# SCH_clock1_2025-09-26.net
KiCad netlist of a schematic drawn in EasyEDA
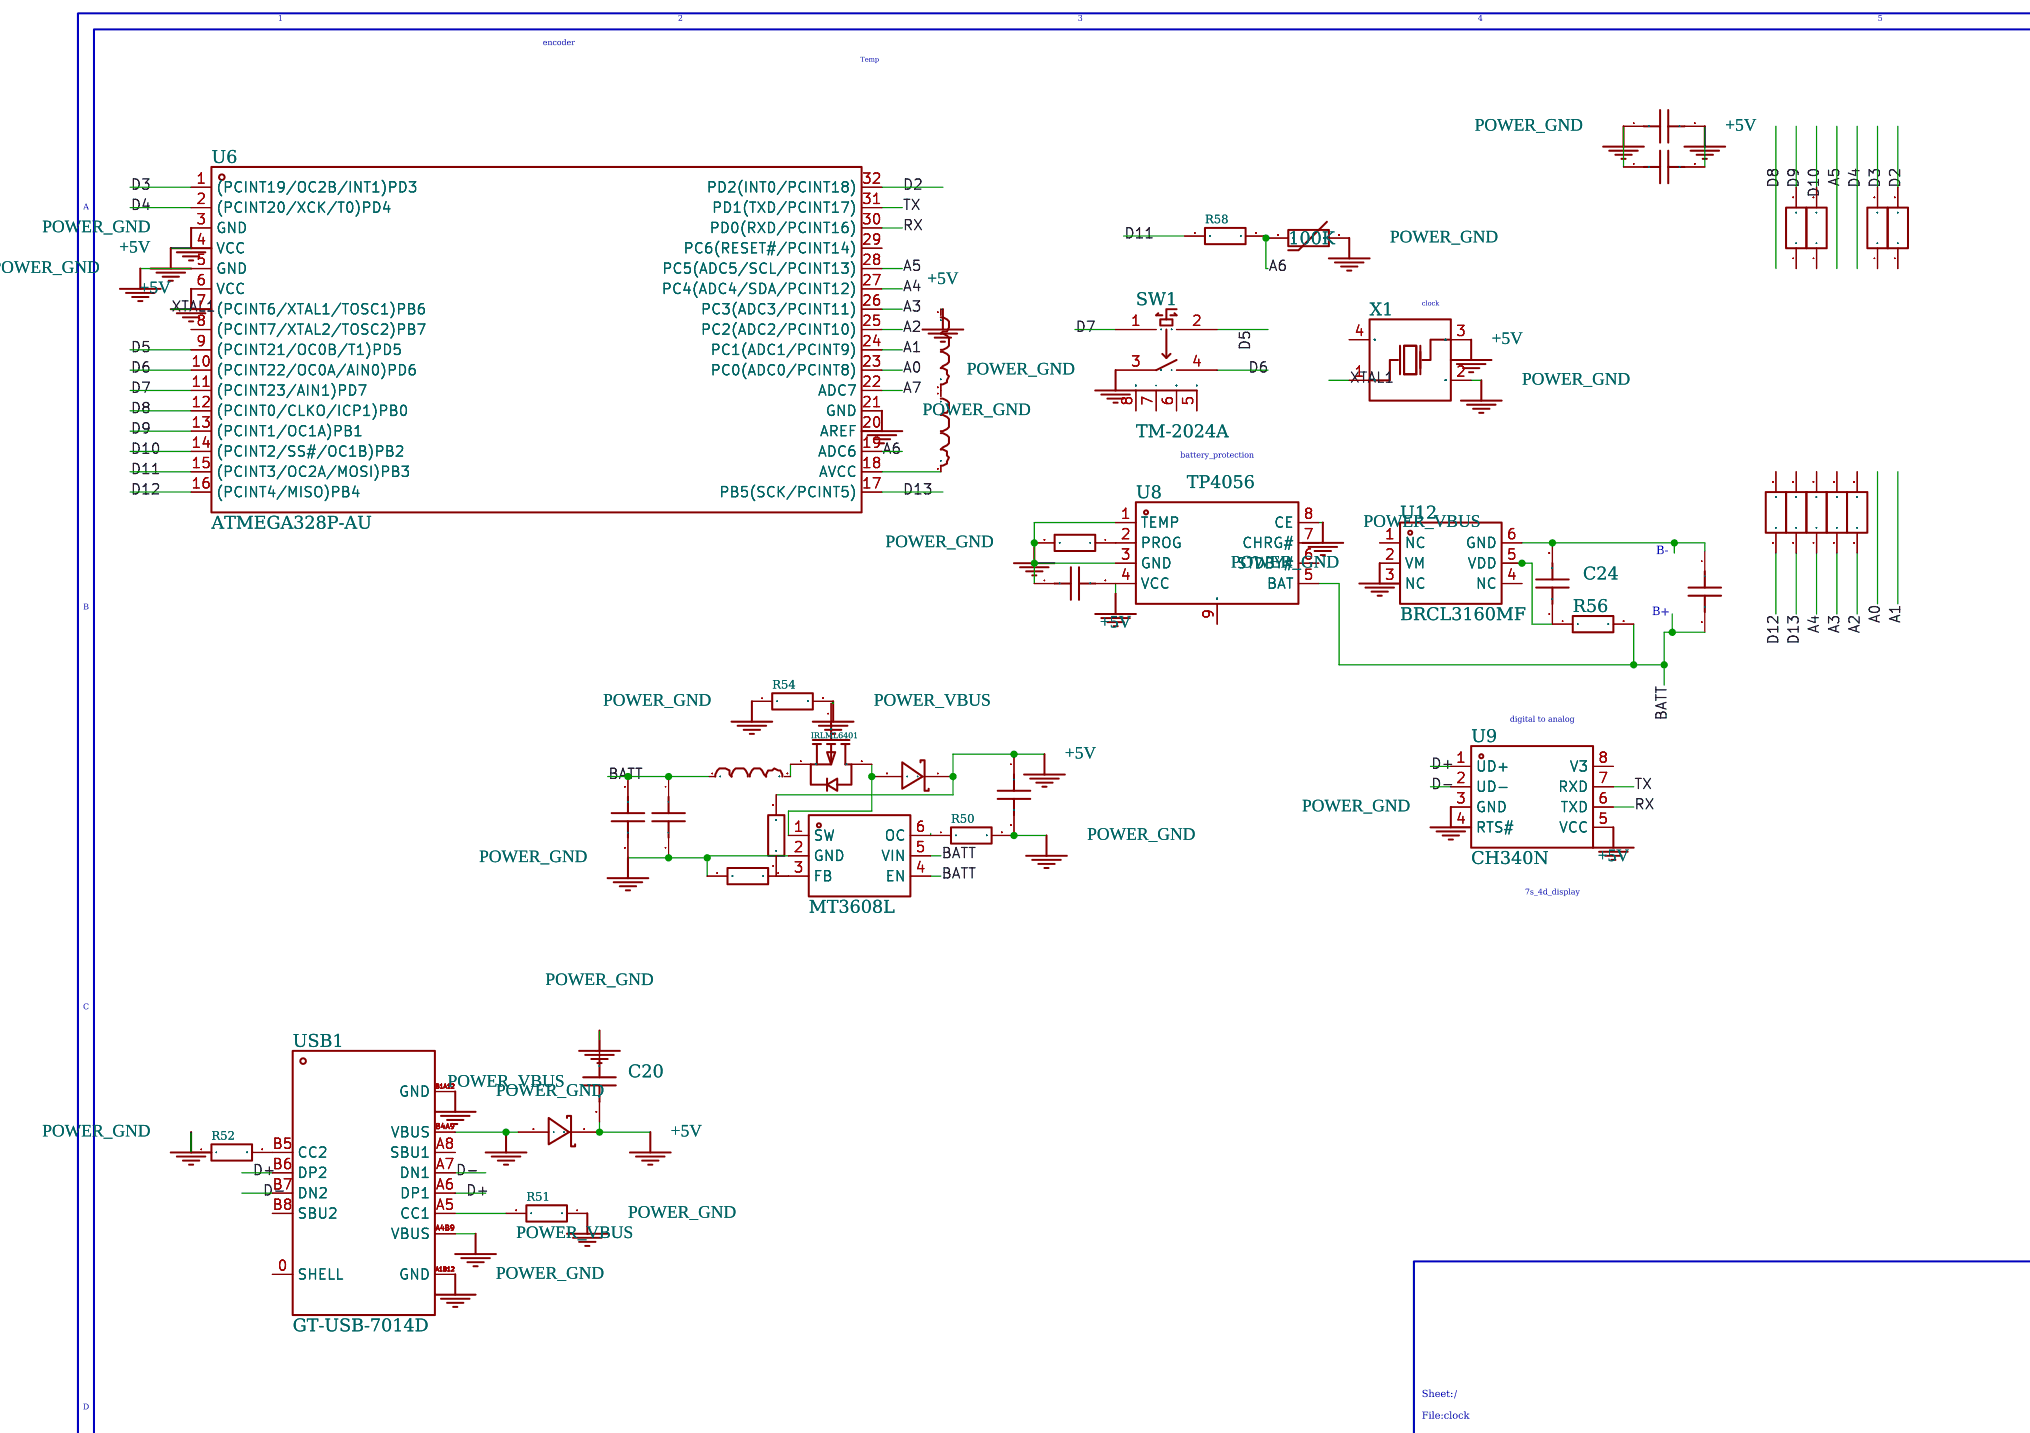
[diagram p0: schematic sheet]

(export (version "E")
  (design (tool "Eeschema 10.0.6"))
  (components
    (comp (ref "100K")
      (value "NCP03WF104F05RL")
      (fields (field (name "Manufacturer") "muRata(村田)"))
      (libsource (lib "") (part "Unknown_635_-660"))
    )
    (comp (ref "C15")
      (value "4.7uF")
      (fields
        (field (name "Manufacturer Part") "CL05A475MQ5NRNC")
        (field (name "Manufacturer") "SAMSUNG(三星)")
      )
      (libsource (lib "") (part "Unknown_300_-375"))
    )
    (comp (ref "C16")
      (value "4.7uF")
      (fields
        (field (name "Manufacturer Part") "CL05A475MQ5NRNC")
        (field (name "Manufacturer") "SAMSUNG(三星)")
      )
      (libsource (lib "") (part "Unknown_320_-375"))
    )
    (comp (ref "C19")
      (value "4.7uF")
      (fields
        (field (name "Manufacturer Part") "CL05A475MQ5NRNC")
        (field (name "Manufacturer") "SAMSUNG(三星)")
      )
      (libsource (lib "") (part "Unknown_520_-490"))
    )
    (comp (ref "C20")
      (value "4.7uF")
      (fields
        (field (name "Manufacturer Part") "CL05A475MQ5NRNC")
        (field (name "Manufacturer") "SAMSUNG(三星)")
      )
      (libsource (lib "") (part "Unknown_286_-245"))
    )
    (comp (ref "C21")
      (value "4.7uF")
      (fields
        (field (name "Manufacturer Part") "CL05A475MQ5NRNC")
        (field (name "Manufacturer") "SAMSUNG(三星)")
      )
      (libsource (lib "") (part "Unknown_490_-386"))
    )
    (comp (ref "C24")
      (value "100nF")
      (fields
        (field (name "Manufacturer Part") "FCC0402B104K160AT")
        (field (name "Manufacturer") "FOJAN(富捷)")
      )
      (libsource (lib "") (part "Unknown_755_-490"))
    )
    (comp (ref "C25")
      (value "4.7uF")
      (fields
        (field (name "Manufacturer Part") "CL05A475MQ5NRNC")
        (field (name "Manufacturer") "SAMSUNG(三星)")
      )
      (libsource (lib "") (part "Unknown_810_-715"))
    )
    (comp (ref "C27")
      (value "4.7uF")
      (fields
        (field (name "Manufacturer Part") "CL05A475MQ5NRNC")
        (field (name "Manufacturer") "SAMSUNG(三星)")
      )
      (libsource (lib "") (part "Unknown_810_-695"))
    )
    (comp (ref "C28")
      (value "4.7uF")
      (fields
        (field (name "Manufacturer Part") "CL05A475MQ5NRNC")
        (field (name "Manufacturer") "SAMSUNG(三星)")
      )
      (libsource (lib "") (part "Unknown_830_-486"))
    )
    (comp (ref "D5")
      (value "DSK34")
      (fields (field (name "Manufacturer") "MDD(辰达半导体)"))
      (libsource (lib "") (part "Unknown_440_-395"))
    )
    (comp (ref "D6")
      (value "DSK34")
      (fields (field (name "Manufacturer") "MDD(辰达半导体)"))
      (libsource (lib "") (part "Unknown_266_-220"))
    )
    (comp (ref "L3")
      (value "4.7uH")
      (fields (field (name "Manufacturer Part") "CMI321609U4R7KT") (field (name "Manufacturer") "FH(风华)"))
      (libsource (lib "") (part "Unknown_360_-395"))
    )
    (comp (ref "L5")
      (value "4.7uH")
      (fields (field (name "Manufacturer Part") "CMI321609U4R7KT") (field (name "Manufacturer") "FH(风华)"))
      (libsource (lib "") (part "Unknown_454_-565"))
    )
    (comp (ref "L6")
      (value "4.7uH")
      (fields (field (name "Manufacturer Part") "CMI321609U4R7KT") (field (name "Manufacturer") "FH(风华)"))
      (libsource (lib "") (part "Unknown_454_-605"))
    )
    (comp (ref "Q1")
      (value "IRLML6401")
      (fields (field (name "Manufacturer") "Hottech(合科泰)"))
      (libsource (lib "") (part "Unknown_400_-401"))
    )
    (comp (ref "R39")
      (value "1kΩ")
      (fields (field (name "Manufacturer Part") "FRC0603F1001TS") (field (name "Manufacturer") "FOJAN(富捷)"))
      (libsource (lib "") (part "Unknown_875_-665"))
    )
    (comp (ref "R40")
      (value "1kΩ")
      (fields (field (name "Manufacturer Part") "FRC0603F1001TS") (field (name "Manufacturer") "FOJAN(富捷)"))
      (libsource (lib "") (part "Unknown_915_-665"))
    )
    (comp (ref "R41")
      (value "1kΩ")
      (fields (field (name "Manufacturer Part") "FRC0603F1001TS") (field (name "Manufacturer") "FOJAN(富捷)"))
      (libsource (lib "") (part "Unknown_885_-665"))
    )
    (comp (ref "R42")
      (value "1kΩ")
      (fields (field (name "Manufacturer Part") "FRC0603F1001TS") (field (name "Manufacturer") "FOJAN(富捷)"))
      (libsource (lib "") (part "Unknown_905_-525"))
    )
    (comp (ref "R43")
      (value "1kΩ")
      (fields (field (name "Manufacturer Part") "FRC0603F1001TS") (field (name "Manufacturer") "FOJAN(富捷)"))
      (libsource (lib "") (part "Unknown_895_-525"))
    )
    (comp (ref "R44")
      (value "1kΩ")
      (fields (field (name "Manufacturer Part") "FRC0603F1001TS") (field (name "Manufacturer") "FOJAN(富捷)"))
      (libsource (lib "") (part "Unknown_925_-665"))
    )
    (comp (ref "R45")
      (value "1kΩ")
      (fields (field (name "Manufacturer Part") "FRC0603F1001TS") (field (name "Manufacturer") "FOJAN(富捷)"))
      (libsource (lib "") (part "Unknown_875_-525"))
    )
    (comp (ref "R46")
      (value "1kΩ")
      (fields (field (name "Manufacturer Part") "FRC0603F1001TS") (field (name "Manufacturer") "FOJAN(富捷)"))
      (libsource (lib "") (part "Unknown_865_-525"))
    )
    (comp (ref "R48")
      (value "2.4kΩ")
      (fields
        (field (name "Manufacturer Part") "0402WGF2401TCE")
        (field (name "Manufacturer") "UNI-ROYAL(厚声)")
      )
      (libsource (lib "") (part "Unknown_520_-510"))
    )
    (comp (ref "R49")
      (value "2.4kΩ")
      (fields
        (field (name "Manufacturer Part") "0402WGF2401TCE")
        (field (name "Manufacturer") "UNI-ROYAL(厚声)")
      )
      (libsource (lib "") (part "Unknown_359_-346"))
    )
    (comp (ref "R50")
      (value "100kΩ")
      (fields
        (field (name "Manufacturer Part") "0402WGF1003TCE")
        (field (name "Manufacturer") "UNI-ROYAL(厚声)")
      )
      (libsource (lib "") (part "Unknown_469_-366"))
    )
    (comp (ref "R51")
      (value "5.1kΩ")
      (fields
        (field (name "Manufacturer Part") "0402WGF5101TCE")
        (field (name "Manufacturer") "UNI-ROYAL(厚声)")
      )
      (libsource (lib "") (part "Unknown_260_-180"))
    )
    (comp (ref "R52")
      (value "5.1kΩ")
      (fields
        (field (name "Manufacturer Part") "0402WGF5101TCE")
        (field (name "Manufacturer") "UNI-ROYAL(厚声)")
      )
      (libsource (lib "") (part "Unknown_105_-210"))
    )
    (comp (ref "R53")
      (value "20kΩ")
      (fields
        (field (name "Manufacturer Part") "0402WGF2002TCE")
        (field (name "Manufacturer") "UNI-ROYAL(厚声)")
      )
      (libsource (lib "") (part "Unknown_373_-366"))
    )
    (comp (ref "R54")
      (value "5.1kΩ")
      (fields
        (field (name "Manufacturer Part") "0402WGF5101TCE")
        (field (name "Manufacturer") "UNI-ROYAL(厚声)")
      )
      (libsource (lib "") (part "Unknown_381_-432"))
    )
    (comp (ref "R56")
      (value "100Ω")
      (fields
        (field (name "Manufacturer Part") "0402WGF1000TCE")
        (field (name "Manufacturer") "UNI-ROYAL(厚声)")
      )
      (libsource (lib "") (part "Unknown_775_-470"))
    )
    (comp (ref "R57")
      (value "1kΩ")
      (fields (field (name "Manufacturer Part") "FRC0603F1001TS") (field (name "Manufacturer") "FOJAN(富捷)"))
      (libsource (lib "") (part "Unknown_885_-525"))
    )
    (comp (ref "R58")
      (value "100kΩ")
      (fields
        (field (name "Manufacturer Part") "0402WGF1003TCE")
        (field (name "Manufacturer") "UNI-ROYAL(厚声)")
      )
      (libsource (lib "") (part "Unknown_594_-661"))
    )
    (comp (ref "SW1")
      (value "TM-2024A")
      (fields (field (name "Manufacturer") "XKB Connection(中国星坤)"))
      (libsource (lib "") (part "Unknown_570_-595"))
    )
    (comp (ref "U6")
      (value "ATMEGA328P-AU")
      (fields (field (name "Manufacturer") "MICROCHIP(美国微芯)"))
      (libsource (lib "") (part "Unknown_255_-610"))
    )
    (comp (ref "U8")
      (value "TP4056")
      (fields (field (name "Manufacturer") "TDSEMIC(拓电半导体)"))
      (libsource (lib "") (part "Unknown_590_-505"))
    )
    (comp (ref "U9")
      (value "CH340N")
      (fields (field (name "Manufacturer") "WCH(南京沁恒)"))
      (libsource (lib "") (part "Unknown_745_-380"))
    )
    (comp (ref "U10")
      (value "MT3608L")
      (fields (field (name "Manufacturer") "西安航天民芯"))
      (libsource (lib "") (part "Unknown_414_-356"))
    )
    (comp (ref "U12")
      (value "BRCL3160MF")
      (fields (field (name "Manufacturer") "BLUE ROCKET(蓝箭)"))
      (libsource (lib "") (part "Unknown_705_-500"))
    )
    (comp (ref "USB1")
      (value "GT-USB-7014D")
      (fields (field (name "Manufacturer") "G-Switch(品赞)"))
      (libsource (lib "") (part "Unknown_175_-190"))
    )
    (comp (ref "X1")
      (value "16MHz")
      (fields (field (name "Manufacturer Part") "TAXM16M4RLBCCT2T") (field (name "Manufacturer") "YJX(雅晶鑫)"))
      (libsource (lib "") (part "Unknown_685_-600"))
    )
  )
  (nets
    (net (code "1") (name "+5V") (class "Default")
      (node (ref "C19") (pin "2") (pinfunction "2_2") (pintype "unspecified"))
      (node (ref "C20") (pin "2") (pinfunction "2_2") (pintype "unspecified"))
      (node (ref "C21") (pin "1") (pinfunction "1_1") (pintype "unspecified"))
      (node (ref "C25") (pin "2") (pinfunction "2_2") (pintype "unspecified"))
      (node (ref "C27") (pin "2") (pinfunction "2_2") (pintype "unspecified"))
      (node (ref "D5") (pin "1") (pinfunction "K_1") (pintype "unspecified"))
      (node (ref "D6") (pin "1") (pinfunction "K_1") (pintype "unspecified"))
      (node (ref "L6") (pin "1") (pinfunction "1_1") (pintype "unspecified"))
      (node (ref "R53") (pin "2") (pinfunction "2_2") (pintype "unspecified"))
      (node (ref "U6") (pin "4") (pinfunction "VCC_4") (pintype "unspecified"))
      (node (ref "U6") (pin "6") (pinfunction "VCC_6") (pintype "unspecified"))
      (node (ref "U8") (pin "4") (pinfunction "VCC_4") (pintype "unspecified"))
      (node (ref "U9") (pin "5") (pinfunction "VCC_5") (pintype "unspecified"))
      (node (ref "X1") (pin "3") (pinfunction "OSC2_3") (pintype "unspecified"))
    )
    (net (code "2") (name "/A0") (class "Default")
      (node (ref "U6") (pin "23") (pinfunction "PC0(ADC0/PCINT8)_23") (pintype "unspecified"))
    )
    (net (code "3") (name "/A1") (class "Default")
      (node (ref "U6") (pin "24") (pinfunction "PC1(ADC1/PCINT9)_24") (pintype "unspecified"))
    )
    (net (code "4") (name "/A2") (class "Default")
      (node (ref "R42") (pin "1") (pinfunction "1_1") (pintype "unspecified"))
      (node (ref "U6") (pin "25") (pinfunction "PC2(ADC2/PCINT10)_25") (pintype "unspecified"))
    )
    (net (code "5") (name "/A3") (class "Default")
      (node (ref "R43") (pin "1") (pinfunction "1_1") (pintype "unspecified"))
      (node (ref "U6") (pin "26") (pinfunction "PC3(ADC3/PCINT11)_26") (pintype "unspecified"))
    )
    (net (code "6") (name "/A4") (class "Default")
      (node (ref "R57") (pin "1") (pinfunction "1_1") (pintype "unspecified"))
      (node (ref "U6") (pin "27") (pinfunction "PC4(ADC4/SDA/PCINT12)_27") (pintype "unspecified"))
    )
    (net (code "7") (name "/A5") (class "Default")
      (node (ref "U6") (pin "28") (pinfunction "PC5(ADC5/SCL/PCINT13)_28") (pintype "unspecified"))
    )
    (net (code "8") (name "/A6") (class "Default")
      (node (ref "100K") (pin "1") (pinfunction "1_1") (pintype "unspecified"))
      (node (ref "R58") (pin "2") (pinfunction "2_2") (pintype "unspecified"))
      (node (ref "U6") (pin "19") (pinfunction "ADC6_19") (pintype "unspecified"))
    )
    (net (code "9") (name "/A7") (class "Default")
      (node (ref "U6") (pin "22") (pinfunction "ADC7_22") (pintype "unspecified"))
    )
    (net (code "10") (name "/BATT") (class "Default")
      (node (ref "C15") (pin "1") (pinfunction "1_1") (pintype "unspecified"))
      (node (ref "C16") (pin "1") (pinfunction "1_1") (pintype "unspecified"))
      (node (ref "C28") (pin "2") (pinfunction "2_2") (pintype "unspecified"))
      (node (ref "L3") (pin "1") (pinfunction "1_1") (pintype "unspecified"))
      (node (ref "R56") (pin "2") (pinfunction "2_2") (pintype "unspecified"))
      (node (ref "U10") (pin "4") (pinfunction "EN_4") (pintype "unspecified"))
      (node (ref "U10") (pin "5") (pinfunction "VIN_5") (pintype "unspecified"))
      (node (ref "U8") (pin "5") (pinfunction "BAT_5") (pintype "unspecified"))
    )
    (net (code "11") (name "/D+") (class "Default")
      (node (ref "U9") (pin "1") (pinfunction "UD+_1") (pintype "unspecified"))
      (node (ref "USB1") (pin "A6") (pinfunction "DP1_A6") (pintype "unspecified"))
      (node (ref "USB1") (pin "B6") (pinfunction "DP2_B6") (pintype "unspecified"))
    )
    (net (code "12") (name "/D-") (class "Default")
      (node (ref "U9") (pin "2") (pinfunction "UD-_2") (pintype "unspecified"))
      (node (ref "USB1") (pin "A7") (pinfunction "DN1_A7") (pintype "unspecified"))
      (node (ref "USB1") (pin "B7") (pinfunction "DN2_B7") (pintype "unspecified"))
    )
    (net (code "13") (name "/D2") (class "Default")
      (node (ref "R44") (pin "2") (pinfunction "2_2") (pintype "unspecified"))
      (node (ref "U6") (pin "32") (pinfunction "PD2(INT0/PCINT18)_32") (pintype "unspecified"))
    )
    (net (code "14") (name "/D3") (class "Default")
      (node (ref "R40") (pin "2") (pinfunction "2_2") (pintype "unspecified"))
      (node (ref "U6") (pin "1") (pinfunction "(PCINT19/OC2B/INT1)PD3_1") (pintype "unspecified"))
    )
    (net (code "15") (name "/D4") (class "Default")
      (node (ref "U6") (pin "2") (pinfunction "(PCINT20/XCK/T0)PD4_2") (pintype "unspecified"))
    )
    (net (code "16") (name "/D5") (class "Default")
      (node (ref "SW1") (pin "2") (pinfunction "2_2") (pintype "unspecified"))
      (node (ref "U6") (pin "9") (pinfunction "(PCINT21/OC0B/T1)PD5_9") (pintype "unspecified"))
    )
    (net (code "17") (name "/D6") (class "Default")
      (node (ref "SW1") (pin "4") (pinfunction "4_4") (pintype "unspecified"))
      (node (ref "U6") (pin "10") (pinfunction "(PCINT22/OC0A/AIN0)PD6_10") (pintype "unspecified"))
    )
    (net (code "18") (name "/D7") (class "Default")
      (node (ref "SW1") (pin "1") (pinfunction "1_1") (pintype "unspecified"))
      (node (ref "U6") (pin "11") (pinfunction "(PCINT23/AIN1)PD7_11") (pintype "unspecified"))
    )
    (net (code "19") (name "/D8") (class "Default")
      (node (ref "U6") (pin "12") (pinfunction "(PCINT0/CLKO/ICP1)PB0_12") (pintype "unspecified"))
    )
    (net (code "20") (name "/D9") (class "Default")
      (node (ref "R39") (pin "2") (pinfunction "2_2") (pintype "unspecified"))
      (node (ref "U6") (pin "13") (pinfunction "(PCINT1/OC1A)PB1_13") (pintype "unspecified"))
    )
    (net (code "21") (name "/D10") (class "Default")
      (node (ref "R41") (pin "2") (pinfunction "2_2") (pintype "unspecified"))
      (node (ref "U6") (pin "14") (pinfunction "(PCINT2/SS#/OC1B)PB2_14") (pintype "unspecified"))
    )
    (net (code "22") (name "/D11") (class "Default")
      (node (ref "R58") (pin "1") (pinfunction "1_1") (pintype "unspecified"))
      (node (ref "U6") (pin "15") (pinfunction "(PCINT3/OC2A/MOSI)PB3_15") (pintype "unspecified"))
    )
    (net (code "23") (name "/D12") (class "Default")
      (node (ref "R46") (pin "1") (pinfunction "1_1") (pintype "unspecified"))
      (node (ref "U6") (pin "16") (pinfunction "(PCINT4/MISO)PB4_16") (pintype "unspecified"))
    )
    (net (code "24") (name "/D13") (class "Default")
      (node (ref "R45") (pin "1") (pinfunction "1_1") (pintype "unspecified"))
      (node (ref "U6") (pin "17") (pinfunction "PB5(SCK/PCINT5)_17") (pintype "unspecified"))
    )
    (net (code "25") (name "/RX") (class "Default")
      (node (ref "U6") (pin "30") (pinfunction "PD0(RXD/PCINT16)_30") (pintype "unspecified"))
      (node (ref "U9") (pin "6") (pinfunction "TXD_6") (pintype "unspecified"))
    )
    (net (code "26") (name "/TX") (class "Default")
      (node (ref "U6") (pin "31") (pinfunction "PD1(TXD/PCINT17)_31") (pintype "unspecified"))
      (node (ref "U9") (pin "7") (pinfunction "RXD_7") (pintype "unspecified"))
    )
    (net (code "27") (name "/XTAL1") (class "Default")
      (node (ref "U6") (pin "7") (pinfunction "(PCINT6/XTAL1/TOSC1)PB6_7") (pintype "unspecified"))
      (node (ref "X1") (pin "1") (pinfunction "OSC1_1") (pintype "unspecified"))
    )
    (net (code "28") (name "Net-(D5-A)") (class "Default")
      (node (ref "D5") (pin "2") (pinfunction "A_2") (pintype "unspecified"))
      (node (ref "Q1") (pin "3") (pinfunction "D_3") (pintype "unspecified"))
      (node (ref "U10") (pin "1") (pinfunction "SW_1") (pintype "unspecified"))
    )
    (net (code "29") (name "Net-(L5-Pad1)") (class "Default")
      (node (ref "L5") (pin "1") (pinfunction "1_1") (pintype "unspecified"))
      (node (ref "L6") (pin "2") (pinfunction "2_2") (pintype "unspecified"))
    )
    (net (code "30") (name "Net-(Q1-S)") (class "Default")
      (node (ref "L3") (pin "2") (pinfunction "2_2") (pintype "unspecified"))
      (node (ref "Q1") (pin "2") (pinfunction "S_2") (pintype "unspecified"))
    )
    (net (code "31") (name "Net-(U6-AVCC)") (class "Default")
      (node (ref "L5") (pin "2") (pinfunction "2_2") (pintype "unspecified"))
      (node (ref "U6") (pin "18") (pinfunction "AVCC_18") (pintype "unspecified"))
    )
    (net (code "32") (name "Net-(U8-PROG)") (class "Default")
      (node (ref "R48") (pin "1") (pinfunction "1_1") (pintype "unspecified"))
      (node (ref "U8") (pin "2") (pinfunction "PROG_2") (pintype "unspecified"))
    )
    (net (code "33") (name "Net-(U10-FB)") (class "Default")
      (node (ref "R49") (pin "1") (pinfunction "1_1") (pintype "unspecified"))
      (node (ref "R53") (pin "1") (pinfunction "1_1") (pintype "unspecified"))
      (node (ref "U10") (pin "3") (pinfunction "FB_3") (pintype "unspecified"))
    )
    (net (code "34") (name "Net-(U10-OC)") (class "Default")
      (node (ref "R50") (pin "1") (pinfunction "1_1") (pintype "unspecified"))
      (node (ref "U10") (pin "6") (pinfunction "OC_6") (pintype "unspecified"))
    )
    (net (code "35") (name "Net-(U12-GND)") (class "Default")
      (node (ref "C24") (pin "2") (pinfunction "2_2") (pintype "unspecified"))
      (node (ref "C28") (pin "1") (pinfunction "1_1") (pintype "unspecified"))
      (node (ref "U12") (pin "6") (pinfunction "GND_6") (pintype "unspecified"))
    )
    (net (code "36") (name "Net-(U12-VDD)") (class "Default")
      (node (ref "C24") (pin "1") (pinfunction "1_1") (pintype "unspecified"))
      (node (ref "R56") (pin "1") (pinfunction "1_1") (pintype "unspecified"))
      (node (ref "U12") (pin "5") (pinfunction "VDD_5") (pintype "unspecified"))
    )
    (net (code "37") (name "Net-(USB1-CC1)") (class "Default")
      (node (ref "R51") (pin "2") (pinfunction "2_2") (pintype "unspecified"))
      (node (ref "USB1") (pin "A5") (pinfunction "CC1_A5") (pintype "unspecified"))
    )
    (net (code "38") (name "Net-(USB1-CC2)") (class "Default")
      (node (ref "R52") (pin "2") (pinfunction "2_2") (pintype "unspecified"))
      (node (ref "USB1") (pin "B5") (pinfunction "CC2_B5") (pintype "unspecified"))
    )
    (net (code "39") (name "POWER_GND") (class "Default")
      (node (ref "100K") (pin "2") (pinfunction "2_2") (pintype "unspecified"))
      (node (ref "C15") (pin "2") (pinfunction "2_2") (pintype "unspecified"))
      (node (ref "C16") (pin "2") (pinfunction "2_2") (pintype "unspecified"))
      (node (ref "C19") (pin "1") (pinfunction "1_1") (pintype "unspecified"))
      (node (ref "C20") (pin "1") (pinfunction "1_1") (pintype "unspecified"))
      (node (ref "C21") (pin "2") (pinfunction "2_2") (pintype "unspecified"))
      (node (ref "C25") (pin "1") (pinfunction "1_1") (pintype "unspecified"))
      (node (ref "C27") (pin "1") (pinfunction "1_1") (pintype "unspecified"))
      (node (ref "R48") (pin "2") (pinfunction "2_2") (pintype "unspecified"))
      (node (ref "R49") (pin "2") (pinfunction "2_2") (pintype "unspecified"))
      (node (ref "R50") (pin "2") (pinfunction "2_2") (pintype "unspecified"))
      (node (ref "R51") (pin "1") (pinfunction "1_1") (pintype "unspecified"))
      (node (ref "R52") (pin "1") (pinfunction "1_1") (pintype "unspecified"))
      (node (ref "R54") (pin "1") (pinfunction "1_1") (pintype "unspecified"))
      (node (ref "SW1") (pin "3") (pinfunction "3_3") (pintype "unspecified"))
      (node (ref "U10") (pin "2") (pinfunction "GND_2") (pintype "unspecified"))
      (node (ref "U12") (pin "2") (pinfunction "VM_2") (pintype "unspecified"))
      (node (ref "U6") (pin "21") (pinfunction "GND_21") (pintype "unspecified"))
      (node (ref "U6") (pin "3") (pinfunction "GND_3") (pintype "unspecified"))
      (node (ref "U6") (pin "5") (pinfunction "GND_5") (pintype "unspecified"))
      (node (ref "U8") (pin "1") (pinfunction "TEMP_1") (pintype "unspecified"))
      (node (ref "U8") (pin "3") (pinfunction "GND_3") (pintype "unspecified"))
      (node (ref "U9") (pin "3") (pinfunction "GND_3") (pintype "unspecified"))
      (node (ref "USB1") (pin "A1B12") (pinfunction "GND_A1B12") (pintype "unspecified"))
      (node (ref "USB1") (pin "B1A12") (pinfunction "GND_B1A12") (pintype "unspecified"))
      (node (ref "X1") (pin "2") (pinfunction "GND_2") (pintype "unspecified"))
    )
    (net (code "40") (name "POWER_VBUS") (class "Default")
      (node (ref "D6") (pin "2") (pinfunction "A_2") (pintype "unspecified"))
      (node (ref "Q1") (pin "1") (pinfunction "G_1") (pintype "unspecified"))
      (node (ref "R54") (pin "2") (pinfunction "2_2") (pintype "unspecified"))
      (node (ref "U8") (pin "8") (pinfunction "CE_8") (pintype "unspecified"))
      (node (ref "USB1") (pin "A4B9") (pinfunction "VBUS_A4B9") (pintype "unspecified"))
      (node (ref "USB1") (pin "B4A9") (pinfunction "VBUS_B4A9") (pintype "unspecified"))
    )
    (net (code "41") (name "unconnected-(R39-Pad1)") (class "Default")
      (node (ref "R39") (pin "1") (pinfunction "1_1") (pintype "unspecified"))
    )
    (net (code "42") (name "unconnected-(R40-Pad1)") (class "Default")
      (node (ref "R40") (pin "1") (pinfunction "1_1") (pintype "unspecified"))
    )
    (net (code "43") (name "unconnected-(R41-Pad1)") (class "Default")
      (node (ref "R41") (pin "1") (pinfunction "1_1") (pintype "unspecified"))
    )
    (net (code "44") (name "unconnected-(R42-Pad2)") (class "Default")
      (node (ref "R42") (pin "2") (pinfunction "2_2") (pintype "unspecified"))
    )
    (net (code "45") (name "unconnected-(R43-Pad2)") (class "Default")
      (node (ref "R43") (pin "2") (pinfunction "2_2") (pintype "unspecified"))
    )
    (net (code "46") (name "unconnected-(R44-Pad1)") (class "Default")
      (node (ref "R44") (pin "1") (pinfunction "1_1") (pintype "unspecified"))
    )
    (net (code "47") (name "unconnected-(R45-Pad2)") (class "Default")
      (node (ref "R45") (pin "2") (pinfunction "2_2") (pintype "unspecified"))
    )
    (net (code "48") (name "unconnected-(R46-Pad2)") (class "Default")
      (node (ref "R46") (pin "2") (pinfunction "2_2") (pintype "unspecified"))
    )
    (net (code "49") (name "unconnected-(R57-Pad2)") (class "Default")
      (node (ref "R57") (pin "2") (pinfunction "2_2") (pintype "unspecified"))
    )
    (net (code "50") (name "unconnected-(SW1-Pad5)") (class "Default")
      (node (ref "SW1") (pin "5") (pinfunction "5_5") (pintype "unspecified"))
    )
    (net (code "51") (name "unconnected-(SW1-Pad6)") (class "Default")
      (node (ref "SW1") (pin "6") (pinfunction "6_6") (pintype "unspecified"))
    )
    (net (code "52") (name "unconnected-(SW1-Pad7)") (class "Default")
      (node (ref "SW1") (pin "7") (pinfunction "7_7") (pintype "unspecified"))
    )
    (net (code "53") (name "unconnected-(SW1-Pad8)") (class "Default")
      (node (ref "SW1") (pin "8") (pinfunction "8_8") (pintype "unspecified"))
    )
    (net (code "54") (name "unconnected-(U6-(PCINT7{slash}XTAL2{slash}TOSC2)PB7-Pad8)") (class "Default")
      (node (ref "U6") (pin "8") (pinfunction "(PCINT7/XTAL2/TOSC2)PB7_8") (pintype "unspecified"))
    )
    (net (code "55") (name "unconnected-(U6-AREF-Pad20)") (class "Default")
      (node (ref "U6") (pin "20") (pinfunction "AREF_20") (pintype "unspecified"))
    )
    (net (code "56") (name "unconnected-(U6-PC6(RESET#{slash}PCINT14)-Pad29)") (class "Default")
      (node (ref "U6") (pin "29") (pinfunction "PC6(RESET#/PCINT14)_29") (pintype "unspecified"))
    )
    (net (code "57") (name "unconnected-(U8-CHRG#-Pad7)") (class "Default")
      (node (ref "U8") (pin "7") (pinfunction "CHRG#_7") (pintype "unspecified"))
    )
    (net (code "58") (name "unconnected-(U8-GND-Pad9)") (class "Default")
      (node (ref "U8") (pin "9") (pinfunction "GND_9") (pintype "unspecified"))
    )
    (net (code "59") (name "unconnected-(U8-STDBY#-Pad6)") (class "Default")
      (node (ref "U8") (pin "6") (pinfunction "STDBY#_6") (pintype "unspecified"))
    )
    (net (code "60") (name "unconnected-(U9-RTS#-Pad4)") (class "Default")
      (node (ref "U9") (pin "4") (pinfunction "RTS#_4") (pintype "unspecified"))
    )
    (net (code "61") (name "unconnected-(U9-V3-Pad8)") (class "Default")
      (node (ref "U9") (pin "8") (pinfunction "V3_8") (pintype "unspecified"))
    )
    (net (code "62") (name "unconnected-(U12-NC-Pad1)") (class "Default")
      (node (ref "U12") (pin "1") (pinfunction "NC_1") (pintype "unspecified"))
    )
    (net (code "63") (name "unconnected-(U12-NC-Pad3)") (class "Default")
      (node (ref "U12") (pin "3") (pinfunction "NC_3") (pintype "unspecified"))
    )
    (net (code "64") (name "unconnected-(U12-NC-Pad4)") (class "Default")
      (node (ref "U12") (pin "4") (pinfunction "NC_4") (pintype "unspecified"))
    )
    (net (code "65") (name "unconnected-(USB1-SBU1-PadA8)") (class "Default")
      (node (ref "USB1") (pin "A8") (pinfunction "SBU1_A8") (pintype "unspecified"))
    )
    (net (code "66") (name "unconnected-(USB1-SBU2-PadB8)") (class "Default")
      (node (ref "USB1") (pin "B8") (pinfunction "SBU2_B8") (pintype "unspecified"))
    )
    (net (code "67") (name "unconnected-(USB1-SHELL-Pad0)") (class "Default")
      (node (ref "USB1") (pin "0") (pinfunction "SHELL_0") (pintype "unspecified"))
    )
    (net (code "68") (name "unconnected-(X1-GND-Pad4)") (class "Default")
      (node (ref "X1") (pin "4") (pinfunction "GND_4") (pintype "unspecified"))
    )
  )
)
